# RPi_SPI_outputs_v04.net
KiCad netlist of a schematic drawn in EAGLE
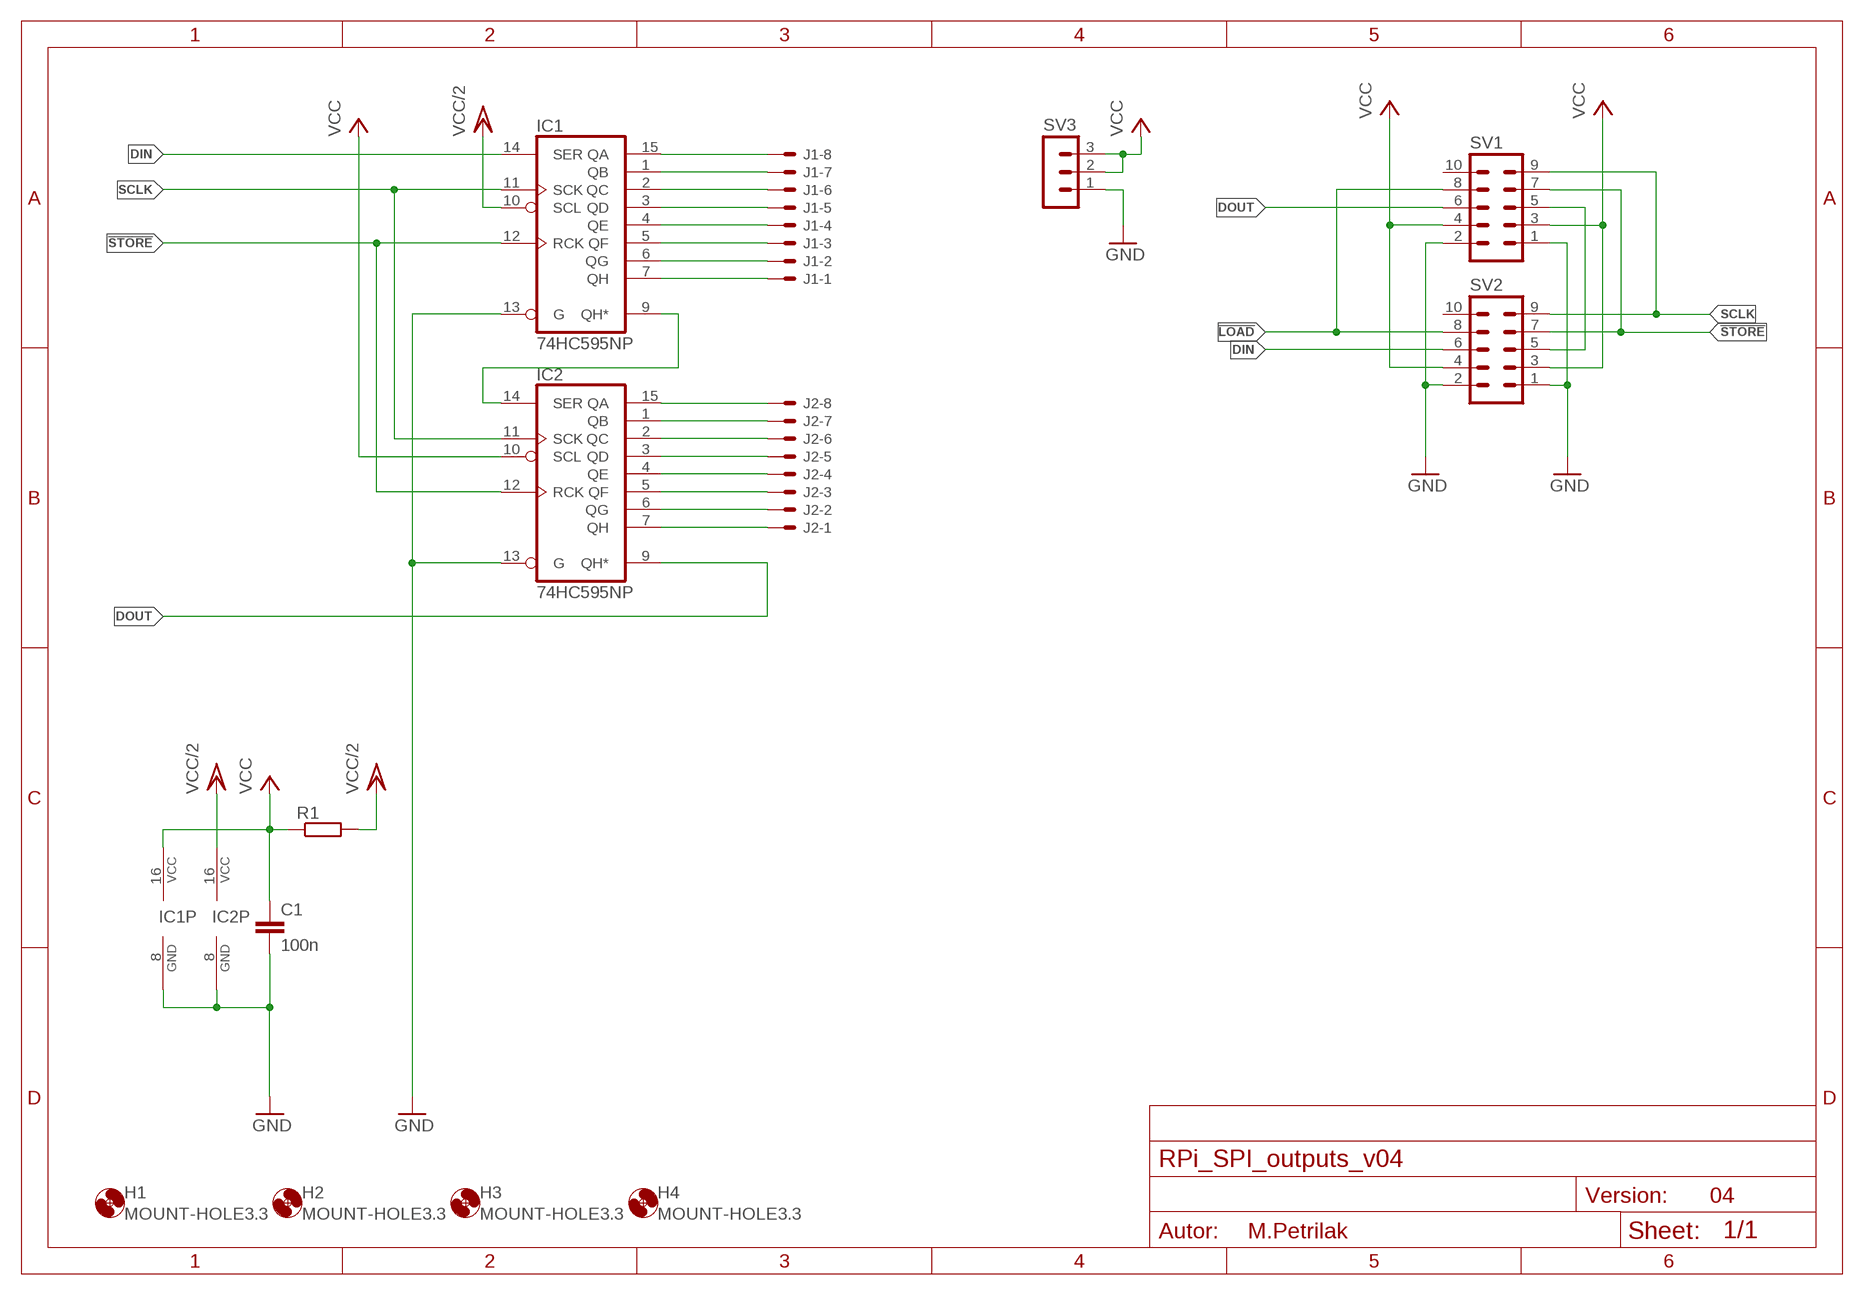
[diagram p0: schematic, sheet 1]

(export (version "E")
  (design (tool "Eeschema 10.0.6"))
  (components
    (comp (ref "C1")
      (value "100n")
      (footprint "eagle-import:C1206")
      (libsource (lib "eagle-import") (part "C-EUC1206"))
    )
    (comp (ref "H1")
      (value "MOUNT-HOLE3.3")
      (footprint "eagle-import:3,3")
      (libsource (lib "eagle-import") (part "MOUNT-HOLE3.3"))
    )
    (comp (ref "H2")
      (value "MOUNT-HOLE3.3")
      (footprint "eagle-import:3,3")
      (libsource (lib "eagle-import") (part "MOUNT-HOLE3.3"))
    )
    (comp (ref "H3")
      (value "MOUNT-HOLE3.3")
      (footprint "eagle-import:3,3")
      (libsource (lib "eagle-import") (part "MOUNT-HOLE3.3"))
    )
    (comp (ref "H4")
      (value "MOUNT-HOLE3.3")
      (footprint "eagle-import:3,3")
      (libsource (lib "eagle-import") (part "MOUNT-HOLE3.3"))
    )
    (comp (ref "IC1")
      (value "74HC595NP")
      (footprint "eagle-import:SOCKET-16")
      (libsource (lib "eagle-import") (part "74595NPHC"))
    )
    (comp (ref "IC2")
      (value "74HC595NP")
      (footprint "eagle-import:SOCKET-16")
      (libsource (lib "eagle-import") (part "74595NPHC"))
    )
    (comp (ref "J1")
      (value "22-05-7088-SPEC-08")
      (footprint "eagle-import:7395-08_SPEC")
      (libsource (lib "eagle-import") (part "22-?-0805-7088-SPEC"))
    )
    (comp (ref "J2")
      (value "22-05-7088-SPEC-08")
      (footprint "eagle-import:7395-08_SPEC")
      (libsource (lib "eagle-import") (part "22-?-0805-7088-SPEC"))
    )
    (comp (ref "R1")
      (value "R-EU_R1206")
      (footprint "eagle-import:R1206")
      (libsource (lib "eagle-import") (part "R-EU_R1206"))
    )
    (comp (ref "SV1")
      (value "ML10")
      (footprint "eagle-import:ML10")
      (libsource (lib "eagle-import") (part "ML10"))
    )
    (comp (ref "SV2")
      (value "ML10")
      (footprint "eagle-import:ML10")
      (libsource (lib "eagle-import") (part "ML10"))
    )
    (comp (ref "SV3")
      (value "MA03-1_NO")
      (footprint "eagle-import:MA03-1_NO")
      (libsource (lib "eagle-import") (part "MA03-1_NO"))
    )
  )
  (nets
    (net (code "1") (name "/~{LOAD}") (class "Default")
      (node (ref "SV1") (pin "8") (pinfunction "8_8") (pintype "passive"))
      (node (ref "SV2") (pin "8") (pinfunction "8_8") (pintype "passive"))
    )
    (net (code "2") (name "/~{STORE}") (class "Default")
      (node (ref "IC1") (pin "12") (pinfunction "RCK_12") (pintype "input"))
      (node (ref "IC2") (pin "12") (pinfunction "RCK_12") (pintype "input"))
      (node (ref "SV1") (pin "7") (pinfunction "7_7") (pintype "passive"))
      (node (ref "SV2") (pin "7") (pinfunction "7_7") (pintype "passive"))
    )
    (net (code "3") (name "DIN") (class "Default")
      (node (ref "IC1") (pin "14") (pinfunction "SER_14") (pintype "input"))
      (node (ref "SV2") (pin "6") (pinfunction "6_6") (pintype "passive"))
    )
    (net (code "4") (name "DOUT") (class "Default")
      (node (ref "IC2") (pin "9") (pinfunction "QH*_9") (pintype "tri_state"))
      (node (ref "SV1") (pin "6") (pinfunction "6_6") (pintype "passive"))
    )
    (net (code "5") (name "GND") (class "Default")
      (node (ref "C1") (pin "2") (pinfunction "2_2") (pintype "passive"))
      (node (ref "IC1") (pin "13") (pinfunction "G_13") (pintype "input"))
      (node (ref "IC1") (pin "8") (pinfunction "GND_8") (pintype "power_in"))
      (node (ref "IC2") (pin "13") (pinfunction "G_13") (pintype "input"))
      (node (ref "IC2") (pin "8") (pinfunction "GND_8") (pintype "power_in"))
      (node (ref "SV1") (pin "1") (pinfunction "1_1") (pintype "passive"))
      (node (ref "SV1") (pin "2") (pinfunction "2_2") (pintype "passive"))
      (node (ref "SV2") (pin "1") (pinfunction "1_1") (pintype "passive"))
      (node (ref "SV2") (pin "2") (pinfunction "2_2") (pintype "passive"))
      (node (ref "SV3") (pin "1") (pinfunction "1_1") (pintype "passive"))
    )
    (net (code "6") (name "Net-(IC1A-QA)") (class "Default")
      (node (ref "IC1") (pin "15") (pinfunction "QA_15") (pintype "tri_state"))
      (node (ref "J1") (pin "8") (pinfunction "S_8") (pintype "passive"))
    )
    (net (code "7") (name "Net-(IC1A-QB)") (class "Default")
      (node (ref "IC1") (pin "1") (pinfunction "QB_1") (pintype "tri_state"))
      (node (ref "J1") (pin "7") (pinfunction "S_7") (pintype "passive"))
    )
    (net (code "8") (name "Net-(IC1A-QC)") (class "Default")
      (node (ref "IC1") (pin "2") (pinfunction "QC_2") (pintype "tri_state"))
      (node (ref "J1") (pin "6") (pinfunction "S_6") (pintype "passive"))
    )
    (net (code "9") (name "Net-(IC1A-QD)") (class "Default")
      (node (ref "IC1") (pin "3") (pinfunction "QD_3") (pintype "tri_state"))
      (node (ref "J1") (pin "5") (pinfunction "S_5") (pintype "passive"))
    )
    (net (code "10") (name "Net-(IC1A-QE)") (class "Default")
      (node (ref "IC1") (pin "4") (pinfunction "QE_4") (pintype "tri_state"))
      (node (ref "J1") (pin "4") (pinfunction "S_4") (pintype "passive"))
    )
    (net (code "11") (name "Net-(IC1A-QF)") (class "Default")
      (node (ref "IC1") (pin "5") (pinfunction "QF_5") (pintype "tri_state"))
      (node (ref "J1") (pin "3") (pinfunction "S_3") (pintype "passive"))
    )
    (net (code "12") (name "Net-(IC1A-QG)") (class "Default")
      (node (ref "IC1") (pin "6") (pinfunction "QG_6") (pintype "tri_state"))
      (node (ref "J1") (pin "2") (pinfunction "S_2") (pintype "passive"))
    )
    (net (code "13") (name "Net-(IC1A-QH)") (class "Default")
      (node (ref "IC1") (pin "7") (pinfunction "QH_7") (pintype "tri_state"))
      (node (ref "J1") (pin "1") (pinfunction "S_1") (pintype "passive"))
    )
    (net (code "14") (name "Net-(IC1A-QH*)") (class "Default")
      (node (ref "IC1") (pin "9") (pinfunction "QH*_9") (pintype "tri_state"))
      (node (ref "IC2") (pin "14") (pinfunction "SER_14") (pintype "input"))
    )
    (net (code "15") (name "Net-(IC2A-QA)") (class "Default")
      (node (ref "IC2") (pin "15") (pinfunction "QA_15") (pintype "tri_state"))
      (node (ref "J2") (pin "8") (pinfunction "S_8") (pintype "passive"))
    )
    (net (code "16") (name "Net-(IC2A-QB)") (class "Default")
      (node (ref "IC2") (pin "1") (pinfunction "QB_1") (pintype "tri_state"))
      (node (ref "J2") (pin "7") (pinfunction "S_7") (pintype "passive"))
    )
    (net (code "17") (name "Net-(IC2A-QC)") (class "Default")
      (node (ref "IC2") (pin "2") (pinfunction "QC_2") (pintype "tri_state"))
      (node (ref "J2") (pin "6") (pinfunction "S_6") (pintype "passive"))
    )
    (net (code "18") (name "Net-(IC2A-QD)") (class "Default")
      (node (ref "IC2") (pin "3") (pinfunction "QD_3") (pintype "tri_state"))
      (node (ref "J2") (pin "5") (pinfunction "S_5") (pintype "passive"))
    )
    (net (code "19") (name "Net-(IC2A-QE)") (class "Default")
      (node (ref "IC2") (pin "4") (pinfunction "QE_4") (pintype "tri_state"))
      (node (ref "J2") (pin "4") (pinfunction "S_4") (pintype "passive"))
    )
    (net (code "20") (name "Net-(IC2A-QF)") (class "Default")
      (node (ref "IC2") (pin "5") (pinfunction "QF_5") (pintype "tri_state"))
      (node (ref "J2") (pin "3") (pinfunction "S_3") (pintype "passive"))
    )
    (net (code "21") (name "Net-(IC2A-QG)") (class "Default")
      (node (ref "IC2") (pin "6") (pinfunction "QG_6") (pintype "tri_state"))
      (node (ref "J2") (pin "2") (pinfunction "S_2") (pintype "passive"))
    )
    (net (code "22") (name "Net-(IC2A-QH)") (class "Default")
      (node (ref "IC2") (pin "7") (pinfunction "QH_7") (pintype "tri_state"))
      (node (ref "J2") (pin "1") (pinfunction "S_1") (pintype "passive"))
    )
    (net (code "23") (name "Net-(SV1-Pad5)") (class "Default")
      (node (ref "SV1") (pin "5") (pinfunction "5_5") (pintype "passive"))
      (node (ref "SV2") (pin "5") (pinfunction "5_5") (pintype "passive"))
    )
    (net (code "24") (name "SCLK") (class "Default")
      (node (ref "IC1") (pin "11") (pinfunction "SCK_11") (pintype "input"))
      (node (ref "IC2") (pin "11") (pinfunction "SCK_11") (pintype "input"))
      (node (ref "SV1") (pin "9") (pinfunction "9_9") (pintype "passive"))
      (node (ref "SV2") (pin "9") (pinfunction "9_9") (pintype "passive"))
    )
    (net (code "25") (name "VCC") (class "Default")
      (node (ref "C1") (pin "1") (pinfunction "1_1") (pintype "passive"))
      (node (ref "IC1") (pin "16") (pinfunction "VCC_16") (pintype "power_in"))
      (node (ref "IC2") (pin "10") (pinfunction "SCL_10") (pintype "input"))
      (node (ref "R1") (pin "1") (pinfunction "1_1") (pintype "passive"))
      (node (ref "SV1") (pin "3") (pinfunction "3_3") (pintype "passive"))
      (node (ref "SV1") (pin "4") (pinfunction "4_4") (pintype "passive"))
      (node (ref "SV2") (pin "3") (pinfunction "3_3") (pintype "passive"))
      (node (ref "SV2") (pin "4") (pinfunction "4_4") (pintype "passive"))
      (node (ref "SV3") (pin "2") (pinfunction "2_2") (pintype "passive"))
      (node (ref "SV3") (pin "3") (pinfunction "3_3") (pintype "passive"))
    )
    (net (code "26") (name "VCC{slash}2") (class "Default")
      (node (ref "IC1") (pin "10") (pinfunction "SCL_10") (pintype "input"))
      (node (ref "IC2") (pin "16") (pinfunction "VCC_16") (pintype "power_in"))
      (node (ref "R1") (pin "2") (pinfunction "2_2") (pintype "passive"))
    )
    (net (code "27") (name "unconnected-(SV1-Pad10)") (class "Default")
      (node (ref "SV1") (pin "10") (pinfunction "10_10") (pintype "passive"))
    )
    (net (code "28") (name "unconnected-(SV2-Pad10)") (class "Default")
      (node (ref "SV2") (pin "10") (pinfunction "10_10") (pintype "passive"))
    )
  )
)
